# VerticalKeyStrip.net
KiCad netlist of a schematic drawn in Altium Designer
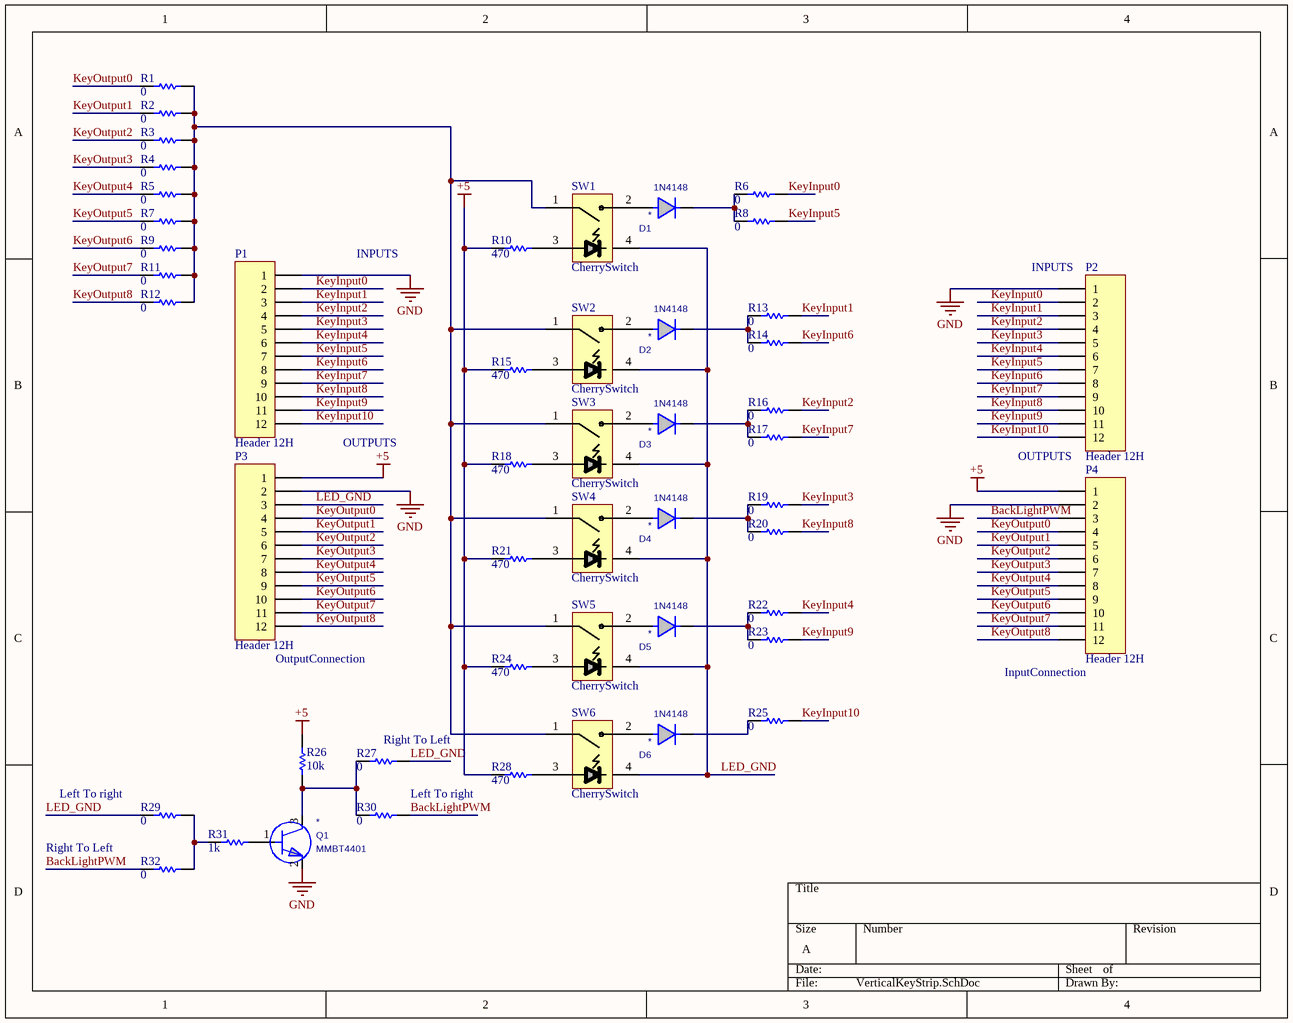
[diagram p0: VerticalKeyStrip.SchDoc]

(export (version "E")
  (design (tool "Eeschema 10.0.6"))
  (components
    (comp (ref "D1")
      (value "1N4148")
      (footprint "DIODE400/60/32")
      (description "Diode, 1N4148, 75V, 0.4 in., DO-35, 150mA, Switching, 500mW, Any")
      (fields (field (name "DNS") "*") (field (name "VOLTAGE") "75V") (field (name "CHECKEDBY") "B. Lyon"))
      (libsource (lib "bome") (part "1N4148"))
    )
    (comp (ref "D2")
      (value "1N4148")
      (footprint "DIODE400/60/32")
      (description "Diode, 1N4148, 75V, 0.4 in., DO-35, 150mA, Switching, 500mW, Any")
      (fields (field (name "DNS") "*") (field (name "VOLTAGE") "75V") (field (name "CHECKEDBY") "B. Lyon"))
      (libsource (lib "bome") (part "1N4148"))
    )
    (comp (ref "D3")
      (value "1N4148")
      (footprint "DIODE400/60/32")
      (description "Diode, 1N4148, 75V, 0.4 in., DO-35, 150mA, Switching, 500mW, Any")
      (fields (field (name "DNS") "*") (field (name "VOLTAGE") "75V") (field (name "CHECKEDBY") "B. Lyon"))
      (libsource (lib "bome") (part "1N4148"))
    )
    (comp (ref "D4")
      (value "1N4148")
      (footprint "DIODE400/60/32")
      (description "Diode, 1N4148, 75V, 0.4 in., DO-35, 150mA, Switching, 500mW, Any")
      (fields (field (name "DNS") "*") (field (name "VOLTAGE") "75V") (field (name "CHECKEDBY") "B. Lyon"))
      (libsource (lib "bome") (part "1N4148"))
    )
    (comp (ref "D5")
      (value "1N4148")
      (footprint "DIODE400/60/32")
      (description "Diode, 1N4148, 75V, 0.4 in., DO-35, 150mA, Switching, 500mW, Any")
      (fields (field (name "DNS") "*") (field (name "VOLTAGE") "75V") (field (name "CHECKEDBY") "B. Lyon"))
      (libsource (lib "bome") (part "1N4148"))
    )
    (comp (ref "D6")
      (value "1N4148")
      (footprint "DIODE400/60/32")
      (description "Diode, 1N4148, 75V, 0.4 in., DO-35, 150mA, Switching, 500mW, Any")
      (fields (field (name "DNS") "*") (field (name "VOLTAGE") "75V") (field (name "CHECKEDBY") "B. Lyon"))
      (libsource (lib "bome") (part "1N4148"))
    )
    (comp (ref "P1")
      (value "Header 12H")
      (footprint "HDR1X12H")
      (description "Header, 12-Pin, Right Angle")
      (fields (field (name "PUBLISHER") "Altium Limited"))
      (libsource (lib "Miscellaneous Connectors") (part "Header 12H"))
    )
    (comp (ref "P2")
      (value "Header 12H")
      (footprint "HDR1X12H")
      (description "Header, 12-Pin, Right Angle")
      (fields (field (name "PUBLISHER") "Altium Limited"))
      (libsource (lib "") (part "Header 12H_1"))
    )
    (comp (ref "P3")
      (value "Header 12H")
      (footprint "HDR1X12H")
      (description "Header, 12-Pin, Right Angle")
      (fields (field (name "PUBLISHER") "Altium Limited"))
      (libsource (lib "Miscellaneous Connectors") (part "Header 12H"))
    )
    (comp (ref "P4")
      (value "Header 12H")
      (footprint "HDR1X12H")
      (description "Header, 12-Pin, Right Angle")
      (fields (field (name "PUBLISHER") "Altium Limited"))
      (libsource (lib "") (part "Header 12H_1"))
    )
    (comp (ref "Q1")
      (value "MMBT4401")
      (footprint "SOT23-3")
      (description "Transistor, MMBT4401, 40V, SOT23-3, 500mA, NPN, Transistor, On Semi: MMBT4401LT1")
      (fields
        (field (name "DNS") "*")
        (field (name "VOLTAGE") "40V")
        (field (name "Comment") "NPN_TRANSISTOR")
        (field (name "CHECKEDBY") "gdeguzman")
        (field (name "CREATEDBY") "Mike Tyger")
        (field (name "LASTUPDATEDBY") "Mike Tyger")
      )
      (libsource (lib "bome") (part "NPN_TRANSISTOR"))
    )
    (comp (ref "R1")
      (value "0")
      (footprint "RESC2012L")
      (description "Semiconductor Resistor")
      (fields (field (name "Comment") "Res Semi") (field (name "PUBLISHER") "Altium Limited"))
      (libsource (lib "Miscellaneous Devices") (part "Res Semi"))
    )
    (comp (ref "R2")
      (value "0")
      (footprint "RESC2012L")
      (description "Semiconductor Resistor")
      (fields (field (name "Comment") "Res Semi") (field (name "PUBLISHER") "Altium Limited"))
      (libsource (lib "Miscellaneous Devices") (part "Res Semi"))
    )
    (comp (ref "R3")
      (value "0")
      (footprint "RESC2012L")
      (description "Semiconductor Resistor")
      (fields (field (name "Comment") "Res Semi") (field (name "PUBLISHER") "Altium Limited"))
      (libsource (lib "Miscellaneous Devices") (part "Res Semi"))
    )
    (comp (ref "R4")
      (value "0")
      (footprint "RESC2012L")
      (description "Semiconductor Resistor")
      (fields (field (name "Comment") "Res Semi") (field (name "PUBLISHER") "Altium Limited"))
      (libsource (lib "Miscellaneous Devices") (part "Res Semi"))
    )
    (comp (ref "R5")
      (value "0")
      (footprint "RESC2012L")
      (description "Semiconductor Resistor")
      (fields (field (name "Comment") "Res Semi") (field (name "PUBLISHER") "Altium Limited"))
      (libsource (lib "Miscellaneous Devices") (part "Res Semi"))
    )
    (comp (ref "R6")
      (value "0")
      (footprint "RESC2012L")
      (description "Semiconductor Resistor")
      (fields (field (name "Comment") "Res Semi") (field (name "PUBLISHER") "Altium Limited"))
      (libsource (lib "Miscellaneous Devices") (part "Res Semi"))
    )
    (comp (ref "R7")
      (value "0")
      (footprint "RESC2012L")
      (description "Semiconductor Resistor")
      (fields (field (name "Comment") "Res Semi") (field (name "PUBLISHER") "Altium Limited"))
      (libsource (lib "Miscellaneous Devices") (part "Res Semi"))
    )
    (comp (ref "R8")
      (value "0")
      (footprint "RESC2012L")
      (description "Semiconductor Resistor")
      (fields (field (name "Comment") "Res Semi") (field (name "PUBLISHER") "Altium Limited"))
      (libsource (lib "Miscellaneous Devices") (part "Res Semi"))
    )
    (comp (ref "R9")
      (value "0")
      (footprint "RESC2012L")
      (description "Semiconductor Resistor")
      (fields (field (name "Comment") "Res Semi") (field (name "PUBLISHER") "Altium Limited"))
      (libsource (lib "Miscellaneous Devices") (part "Res Semi"))
    )
    (comp (ref "R10")
      (value "470")
      (footprint "RESC2012L")
      (description "Semiconductor Resistor")
      (fields (field (name "Comment") "Res Semi") (field (name "PUBLISHER") "Altium Limited"))
      (libsource (lib "Miscellaneous Devices") (part "Res Semi"))
    )
    (comp (ref "R11")
      (value "0")
      (footprint "RESC2012L")
      (description "Semiconductor Resistor")
      (fields (field (name "Comment") "Res Semi") (field (name "PUBLISHER") "Altium Limited"))
      (libsource (lib "Miscellaneous Devices") (part "Res Semi"))
    )
    (comp (ref "R12")
      (value "0")
      (footprint "RESC2012L")
      (description "Semiconductor Resistor")
      (fields (field (name "Comment") "Res Semi") (field (name "PUBLISHER") "Altium Limited"))
      (libsource (lib "Miscellaneous Devices") (part "Res Semi"))
    )
    (comp (ref "R13")
      (value "0")
      (footprint "RESC2012L")
      (description "Semiconductor Resistor")
      (fields (field (name "Comment") "Res Semi") (field (name "PUBLISHER") "Altium Limited"))
      (libsource (lib "Miscellaneous Devices") (part "Res Semi"))
    )
    (comp (ref "R14")
      (value "0")
      (footprint "RESC2012L")
      (description "Semiconductor Resistor")
      (fields (field (name "Comment") "Res Semi") (field (name "PUBLISHER") "Altium Limited"))
      (libsource (lib "Miscellaneous Devices") (part "Res Semi"))
    )
    (comp (ref "R15")
      (value "470")
      (footprint "RESC2012L")
      (description "Semiconductor Resistor")
      (fields (field (name "Comment") "Res Semi") (field (name "PUBLISHER") "Altium Limited"))
      (libsource (lib "Miscellaneous Devices") (part "Res Semi"))
    )
    (comp (ref "R16")
      (value "0")
      (footprint "RESC2012L")
      (description "Semiconductor Resistor")
      (fields (field (name "Comment") "Res Semi") (field (name "PUBLISHER") "Altium Limited"))
      (libsource (lib "Miscellaneous Devices") (part "Res Semi"))
    )
    (comp (ref "R17")
      (value "0")
      (footprint "RESC2012L")
      (description "Semiconductor Resistor")
      (fields (field (name "Comment") "Res Semi") (field (name "PUBLISHER") "Altium Limited"))
      (libsource (lib "Miscellaneous Devices") (part "Res Semi"))
    )
    (comp (ref "R18")
      (value "470")
      (footprint "RESC2012L")
      (description "Semiconductor Resistor")
      (fields (field (name "Comment") "Res Semi") (field (name "PUBLISHER") "Altium Limited"))
      (libsource (lib "Miscellaneous Devices") (part "Res Semi"))
    )
    (comp (ref "R19")
      (value "0")
      (footprint "RESC2012L")
      (description "Semiconductor Resistor")
      (fields (field (name "Comment") "Res Semi") (field (name "PUBLISHER") "Altium Limited"))
      (libsource (lib "Miscellaneous Devices") (part "Res Semi"))
    )
    (comp (ref "R20")
      (value "0")
      (footprint "RESC2012L")
      (description "Semiconductor Resistor")
      (fields (field (name "Comment") "Res Semi") (field (name "PUBLISHER") "Altium Limited"))
      (libsource (lib "Miscellaneous Devices") (part "Res Semi"))
    )
    (comp (ref "R21")
      (value "470")
      (footprint "RESC2012L")
      (description "Semiconductor Resistor")
      (fields (field (name "Comment") "Res Semi") (field (name "PUBLISHER") "Altium Limited"))
      (libsource (lib "Miscellaneous Devices") (part "Res Semi"))
    )
    (comp (ref "R22")
      (value "0")
      (footprint "RESC2012L")
      (description "Semiconductor Resistor")
      (fields (field (name "Comment") "Res Semi") (field (name "PUBLISHER") "Altium Limited"))
      (libsource (lib "Miscellaneous Devices") (part "Res Semi"))
    )
    (comp (ref "R23")
      (value "0")
      (footprint "RESC2012L")
      (description "Semiconductor Resistor")
      (fields (field (name "Comment") "Res Semi") (field (name "PUBLISHER") "Altium Limited"))
      (libsource (lib "Miscellaneous Devices") (part "Res Semi"))
    )
    (comp (ref "R24")
      (value "470")
      (footprint "RESC2012L")
      (description "Semiconductor Resistor")
      (fields (field (name "Comment") "Res Semi") (field (name "PUBLISHER") "Altium Limited"))
      (libsource (lib "Miscellaneous Devices") (part "Res Semi"))
    )
    (comp (ref "R25")
      (value "0")
      (footprint "RESC2012L")
      (description "Semiconductor Resistor")
      (fields (field (name "Comment") "Res Semi") (field (name "PUBLISHER") "Altium Limited"))
      (libsource (lib "Miscellaneous Devices") (part "Res Semi"))
    )
    (comp (ref "R26")
      (value "10k")
      (footprint "RESC2012L")
      (description "Semiconductor Resistor")
      (fields (field (name "Comment") "Res Semi") (field (name "PUBLISHER") "Altium Limited"))
      (libsource (lib "Miscellaneous Devices") (part "Res Semi"))
    )
    (comp (ref "R27")
      (value "0")
      (footprint "RESC2012L")
      (description "Semiconductor Resistor")
      (fields (field (name "Comment") "Res Semi") (field (name "PUBLISHER") "Altium Limited"))
      (libsource (lib "Miscellaneous Devices") (part "Res Semi"))
    )
    (comp (ref "R28")
      (value "470")
      (footprint "RESC2012L")
      (description "Semiconductor Resistor")
      (fields (field (name "Comment") "Res Semi") (field (name "PUBLISHER") "Altium Limited"))
      (libsource (lib "Miscellaneous Devices") (part "Res Semi"))
    )
    (comp (ref "R29")
      (value "0")
      (footprint "RESC2012L")
      (description "Semiconductor Resistor")
      (fields (field (name "Comment") "Res Semi") (field (name "PUBLISHER") "Altium Limited"))
      (libsource (lib "Miscellaneous Devices") (part "Res Semi"))
    )
    (comp (ref "R30")
      (value "0")
      (footprint "RESC2012L")
      (description "Semiconductor Resistor")
      (fields (field (name "Comment") "Res Semi") (field (name "PUBLISHER") "Altium Limited"))
      (libsource (lib "Miscellaneous Devices") (part "Res Semi"))
    )
    (comp (ref "R31")
      (value "1k")
      (footprint "RESC2012L")
      (description "Semiconductor Resistor")
      (fields (field (name "Comment") "Res Semi") (field (name "PUBLISHER") "Altium Limited"))
      (libsource (lib "Miscellaneous Devices") (part "Res Semi"))
    )
    (comp (ref "R32")
      (value "0")
      (footprint "RESC2012L")
      (description "Semiconductor Resistor")
      (fields (field (name "Comment") "Res Semi") (field (name "PUBLISHER") "Altium Limited"))
      (libsource (lib "Miscellaneous Devices") (part "Res Semi"))
    )
    (comp (ref "SW1")
      (value "CherrySwitch")
      (footprint "CherryMxSwitch")
      (description "Cherry MX Switch layout")
      (libsource (lib "mainBoardLib") (part "CherrySwitch"))
    )
    (comp (ref "SW2")
      (value "CherrySwitch")
      (footprint "CherryMxSwitch")
      (description "Cherry MX Switch layout")
      (libsource (lib "mainBoardLib") (part "CherrySwitch"))
    )
    (comp (ref "SW3")
      (value "CherrySwitch")
      (footprint "CherryMxSwitch")
      (description "Cherry MX Switch layout")
      (libsource (lib "mainBoardLib") (part "CherrySwitch"))
    )
    (comp (ref "SW4")
      (value "CherrySwitch")
      (footprint "CherryMxSwitch")
      (description "Cherry MX Switch layout")
      (libsource (lib "mainBoardLib") (part "CherrySwitch"))
    )
    (comp (ref "SW5")
      (value "CherrySwitch")
      (footprint "CherryMxSwitch")
      (description "Cherry MX Switch layout")
      (libsource (lib "mainBoardLib") (part "CherrySwitch"))
    )
    (comp (ref "SW6")
      (value "CherrySwitch")
      (footprint "CherryMxSwitch")
      (description "Cherry MX Switch layout")
      (libsource (lib "mainBoardLib") (part "CherrySwitch"))
    )
  )
  (nets
    (net (code "1") (name "+5") (class "Default")
      (node (ref "P3") (pin "1") (pinfunction "1_1") (pintype "passive"))
      (node (ref "P4") (pin "1") (pinfunction "1_1") (pintype "passive"))
      (node (ref "R10") (pin "1") (pinfunction "1_1") (pintype "passive"))
      (node (ref "R15") (pin "1") (pinfunction "1_1") (pintype "passive"))
      (node (ref "R18") (pin "1") (pinfunction "1_1") (pintype "passive"))
      (node (ref "R21") (pin "1") (pinfunction "1_1") (pintype "passive"))
      (node (ref "R24") (pin "1") (pinfunction "1_1") (pintype "passive"))
      (node (ref "R26") (pin "2") (pinfunction "2_2") (pintype "passive"))
      (node (ref "R28") (pin "1") (pinfunction "1_1") (pintype "passive"))
    )
    (net (code "2") (name "/BackLightPWM") (class "Default")
      (node (ref "P4") (pin "3") (pinfunction "3_3") (pintype "passive"))
      (node (ref "R30") (pin "2") (pinfunction "2_2") (pintype "passive"))
      (node (ref "R32") (pin "1") (pinfunction "1_1") (pintype "passive"))
    )
    (net (code "3") (name "/KeyInput0") (class "Default")
      (node (ref "P1") (pin "2") (pinfunction "2_2") (pintype "passive"))
      (node (ref "P2") (pin "2") (pinfunction "2_2") (pintype "passive"))
      (node (ref "R6") (pin "2") (pinfunction "2_2") (pintype "passive"))
    )
    (net (code "4") (name "/KeyInput1") (class "Default")
      (node (ref "P1") (pin "3") (pinfunction "3_3") (pintype "passive"))
      (node (ref "P2") (pin "3") (pinfunction "3_3") (pintype "passive"))
      (node (ref "R13") (pin "2") (pinfunction "2_2") (pintype "passive"))
    )
    (net (code "5") (name "/KeyInput2") (class "Default")
      (node (ref "P1") (pin "4") (pinfunction "4_4") (pintype "passive"))
      (node (ref "P2") (pin "4") (pinfunction "4_4") (pintype "passive"))
      (node (ref "R16") (pin "2") (pinfunction "2_2") (pintype "passive"))
    )
    (net (code "6") (name "/KeyInput3") (class "Default")
      (node (ref "P1") (pin "5") (pinfunction "5_5") (pintype "passive"))
      (node (ref "P2") (pin "5") (pinfunction "5_5") (pintype "passive"))
      (node (ref "R19") (pin "2") (pinfunction "2_2") (pintype "passive"))
    )
    (net (code "7") (name "/KeyInput4") (class "Default")
      (node (ref "P1") (pin "6") (pinfunction "6_6") (pintype "passive"))
      (node (ref "P2") (pin "6") (pinfunction "6_6") (pintype "passive"))
      (node (ref "R22") (pin "2") (pinfunction "2_2") (pintype "passive"))
    )
    (net (code "8") (name "/KeyInput5") (class "Default")
      (node (ref "P1") (pin "7") (pinfunction "7_7") (pintype "passive"))
      (node (ref "P2") (pin "7") (pinfunction "7_7") (pintype "passive"))
      (node (ref "R8") (pin "2") (pinfunction "2_2") (pintype "passive"))
    )
    (net (code "9") (name "/KeyInput6") (class "Default")
      (node (ref "P1") (pin "8") (pinfunction "8_8") (pintype "passive"))
      (node (ref "P2") (pin "8") (pinfunction "8_8") (pintype "passive"))
      (node (ref "R14") (pin "2") (pinfunction "2_2") (pintype "passive"))
    )
    (net (code "10") (name "/KeyInput7") (class "Default")
      (node (ref "P1") (pin "9") (pinfunction "9_9") (pintype "passive"))
      (node (ref "P2") (pin "9") (pinfunction "9_9") (pintype "passive"))
      (node (ref "R17") (pin "2") (pinfunction "2_2") (pintype "passive"))
    )
    (net (code "11") (name "/KeyInput8") (class "Default")
      (node (ref "P1") (pin "10") (pinfunction "10_10") (pintype "passive"))
      (node (ref "P2") (pin "10") (pinfunction "10_10") (pintype "passive"))
      (node (ref "R20") (pin "2") (pinfunction "2_2") (pintype "passive"))
    )
    (net (code "12") (name "/KeyInput9") (class "Default")
      (node (ref "P1") (pin "11") (pinfunction "11_11") (pintype "passive"))
      (node (ref "P2") (pin "11") (pinfunction "11_11") (pintype "passive"))
      (node (ref "R23") (pin "2") (pinfunction "2_2") (pintype "passive"))
    )
    (net (code "13") (name "/KeyInput10") (class "Default")
      (node (ref "P1") (pin "12") (pinfunction "12_12") (pintype "passive"))
      (node (ref "P2") (pin "12") (pinfunction "12_12") (pintype "passive"))
      (node (ref "R25") (pin "2") (pinfunction "2_2") (pintype "passive"))
    )
    (net (code "14") (name "/KeyOutput0") (class "Default")
      (node (ref "P3") (pin "4") (pinfunction "4_4") (pintype "passive"))
      (node (ref "P4") (pin "4") (pinfunction "4_4") (pintype "passive"))
      (node (ref "R1") (pin "1") (pinfunction "1_1") (pintype "passive"))
    )
    (net (code "15") (name "/KeyOutput1") (class "Default")
      (node (ref "P3") (pin "5") (pinfunction "5_5") (pintype "passive"))
      (node (ref "P4") (pin "5") (pinfunction "5_5") (pintype "passive"))
      (node (ref "R2") (pin "1") (pinfunction "1_1") (pintype "passive"))
    )
    (net (code "16") (name "/KeyOutput2") (class "Default")
      (node (ref "P3") (pin "6") (pinfunction "6_6") (pintype "passive"))
      (node (ref "P4") (pin "6") (pinfunction "6_6") (pintype "passive"))
      (node (ref "R3") (pin "1") (pinfunction "1_1") (pintype "passive"))
    )
    (net (code "17") (name "/KeyOutput3") (class "Default")
      (node (ref "P3") (pin "7") (pinfunction "7_7") (pintype "passive"))
      (node (ref "P4") (pin "7") (pinfunction "7_7") (pintype "passive"))
      (node (ref "R4") (pin "1") (pinfunction "1_1") (pintype "passive"))
    )
    (net (code "18") (name "/KeyOutput4") (class "Default")
      (node (ref "P3") (pin "8") (pinfunction "8_8") (pintype "passive"))
      (node (ref "P4") (pin "8") (pinfunction "8_8") (pintype "passive"))
      (node (ref "R5") (pin "1") (pinfunction "1_1") (pintype "passive"))
    )
    (net (code "19") (name "/KeyOutput5") (class "Default")
      (node (ref "P3") (pin "9") (pinfunction "9_9") (pintype "passive"))
      (node (ref "P4") (pin "9") (pinfunction "9_9") (pintype "passive"))
      (node (ref "R7") (pin "1") (pinfunction "1_1") (pintype "passive"))
    )
    (net (code "20") (name "/KeyOutput6") (class "Default")
      (node (ref "P3") (pin "10") (pinfunction "10_10") (pintype "passive"))
      (node (ref "P4") (pin "10") (pinfunction "10_10") (pintype "passive"))
      (node (ref "R9") (pin "1") (pinfunction "1_1") (pintype "passive"))
    )
    (net (code "21") (name "/KeyOutput7") (class "Default")
      (node (ref "P3") (pin "11") (pinfunction "11_11") (pintype "passive"))
      (node (ref "P4") (pin "11") (pinfunction "11_11") (pintype "passive"))
      (node (ref "R11") (pin "1") (pinfunction "1_1") (pintype "passive"))
    )
    (net (code "22") (name "/KeyOutput8") (class "Default")
      (node (ref "P3") (pin "12") (pinfunction "12_12") (pintype "passive"))
      (node (ref "P4") (pin "12") (pinfunction "12_12") (pintype "passive"))
      (node (ref "R12") (pin "1") (pinfunction "1_1") (pintype "passive"))
    )
    (net (code "23") (name "/LED_GND") (class "Default")
      (node (ref "P3") (pin "3") (pinfunction "3_3") (pintype "passive"))
      (node (ref "R27") (pin "2") (pinfunction "2_2") (pintype "passive"))
      (node (ref "R29") (pin "1") (pinfunction "1_1") (pintype "passive"))
      (node (ref "SW1") (pin "4") (pinfunction "4_4") (pintype "passive"))
      (node (ref "SW2") (pin "4") (pinfunction "4_4") (pintype "passive"))
      (node (ref "SW3") (pin "4") (pinfunction "4_4") (pintype "passive"))
      (node (ref "SW4") (pin "4") (pinfunction "4_4") (pintype "passive"))
      (node (ref "SW5") (pin "4") (pinfunction "4_4") (pintype "passive"))
      (node (ref "SW6") (pin "4") (pinfunction "4_4") (pintype "passive"))
    )
    (net (code "24") (name "GND") (class "Default")
      (node (ref "P1") (pin "1") (pinfunction "1_1") (pintype "passive"))
      (node (ref "P2") (pin "1") (pinfunction "1_1") (pintype "passive"))
      (node (ref "P3") (pin "2") (pinfunction "2_2") (pintype "passive"))
      (node (ref "P4") (pin "2") (pinfunction "2_2") (pintype "passive"))
      (node (ref "Q1") (pin "2") (pinfunction "emitter_2") (pintype "passive"))
    )
    (net (code "25") (name "Net-(D1-ANODE)") (class "Default")
      (node (ref "D1") (pin "2") (pinfunction "ANODE_2") (pintype "passive"))
      (node (ref "SW1") (pin "2") (pinfunction "2_2") (pintype "passive"))
    )
    (net (code "26") (name "Net-(D1-CATHODE)") (class "Default")
      (node (ref "D1") (pin "1") (pinfunction "CATHODE_1") (pintype "passive"))
      (node (ref "R6") (pin "1") (pinfunction "1_1") (pintype "passive"))
      (node (ref "R8") (pin "1") (pinfunction "1_1") (pintype "passive"))
    )
    (net (code "27") (name "Net-(D2-ANODE)") (class "Default")
      (node (ref "D2") (pin "2") (pinfunction "ANODE_2") (pintype "passive"))
      (node (ref "SW2") (pin "2") (pinfunction "2_2") (pintype "passive"))
    )
    (net (code "28") (name "Net-(D2-CATHODE)") (class "Default")
      (node (ref "D2") (pin "1") (pinfunction "CATHODE_1") (pintype "passive"))
      (node (ref "R13") (pin "1") (pinfunction "1_1") (pintype "passive"))
      (node (ref "R14") (pin "1") (pinfunction "1_1") (pintype "passive"))
    )
    (net (code "29") (name "Net-(D3-ANODE)") (class "Default")
      (node (ref "D3") (pin "2") (pinfunction "ANODE_2") (pintype "passive"))
      (node (ref "SW3") (pin "2") (pinfunction "2_2") (pintype "passive"))
    )
    (net (code "30") (name "Net-(D3-CATHODE)") (class "Default")
      (node (ref "D3") (pin "1") (pinfunction "CATHODE_1") (pintype "passive"))
      (node (ref "R16") (pin "1") (pinfunction "1_1") (pintype "passive"))
      (node (ref "R17") (pin "1") (pinfunction "1_1") (pintype "passive"))
    )
    (net (code "31") (name "Net-(D4-ANODE)") (class "Default")
      (node (ref "D4") (pin "2") (pinfunction "ANODE_2") (pintype "passive"))
      (node (ref "SW4") (pin "2") (pinfunction "2_2") (pintype "passive"))
    )
    (net (code "32") (name "Net-(D4-CATHODE)") (class "Default")
      (node (ref "D4") (pin "1") (pinfunction "CATHODE_1") (pintype "passive"))
      (node (ref "R19") (pin "1") (pinfunction "1_1") (pintype "passive"))
      (node (ref "R20") (pin "1") (pinfunction "1_1") (pintype "passive"))
    )
    (net (code "33") (name "Net-(D5-ANODE)") (class "Default")
      (node (ref "D5") (pin "2") (pinfunction "ANODE_2") (pintype "passive"))
      (node (ref "SW5") (pin "2") (pinfunction "2_2") (pintype "passive"))
    )
    (net (code "34") (name "Net-(D5-CATHODE)") (class "Default")
      (node (ref "D5") (pin "1") (pinfunction "CATHODE_1") (pintype "passive"))
      (node (ref "R22") (pin "1") (pinfunction "1_1") (pintype "passive"))
      (node (ref "R23") (pin "1") (pinfunction "1_1") (pintype "passive"))
    )
    (net (code "35") (name "Net-(D6-ANODE)") (class "Default")
      (node (ref "D6") (pin "2") (pinfunction "ANODE_2") (pintype "passive"))
      (node (ref "SW6") (pin "2") (pinfunction "2_2") (pintype "passive"))
    )
    (net (code "36") (name "Net-(D6-CATHODE)") (class "Default")
      (node (ref "D6") (pin "1") (pinfunction "CATHODE_1") (pintype "passive"))
      (node (ref "R25") (pin "1") (pinfunction "1_1") (pintype "passive"))
    )
    (net (code "37") (name "Net-(Q1-base)") (class "Default")
      (node (ref "Q1") (pin "1") (pinfunction "base_1") (pintype "passive"))
      (node (ref "R31") (pin "2") (pinfunction "2_2") (pintype "passive"))
    )
    (net (code "38") (name "Net-(Q1-collector)") (class "Default")
      (node (ref "Q1") (pin "3") (pinfunction "collector_3") (pintype "passive"))
      (node (ref "R26") (pin "1") (pinfunction "1_1") (pintype "passive"))
      (node (ref "R27") (pin "1") (pinfunction "1_1") (pintype "passive"))
      (node (ref "R30") (pin "1") (pinfunction "1_1") (pintype "passive"))
    )
    (net (code "39") (name "Net-(R1-Pad2)") (class "Default")
      (node (ref "R1") (pin "2") (pinfunction "2_2") (pintype "passive"))
      (node (ref "R11") (pin "2") (pinfunction "2_2") (pintype "passive"))
      (node (ref "R12") (pin "2") (pinfunction "2_2") (pintype "passive"))
      (node (ref "R2") (pin "2") (pinfunction "2_2") (pintype "passive"))
      (node (ref "R3") (pin "2") (pinfunction "2_2") (pintype "passive"))
      (node (ref "R4") (pin "2") (pinfunction "2_2") (pintype "passive"))
      (node (ref "R5") (pin "2") (pinfunction "2_2") (pintype "passive"))
      (node (ref "R7") (pin "2") (pinfunction "2_2") (pintype "passive"))
      (node (ref "R9") (pin "2") (pinfunction "2_2") (pintype "passive"))
      (node (ref "SW1") (pin "1") (pinfunction "1_1") (pintype "passive"))
      (node (ref "SW2") (pin "1") (pinfunction "1_1") (pintype "passive"))
      (node (ref "SW3") (pin "1") (pinfunction "1_1") (pintype "passive"))
      (node (ref "SW4") (pin "1") (pinfunction "1_1") (pintype "passive"))
      (node (ref "SW5") (pin "1") (pinfunction "1_1") (pintype "passive"))
      (node (ref "SW6") (pin "1") (pinfunction "1_1") (pintype "passive"))
    )
    (net (code "40") (name "Net-(R10-Pad2)") (class "Default")
      (node (ref "R10") (pin "2") (pinfunction "2_2") (pintype "passive"))
      (node (ref "SW1") (pin "3") (pinfunction "3_3") (pintype "passive"))
    )
    (net (code "41") (name "Net-(R15-Pad2)") (class "Default")
      (node (ref "R15") (pin "2") (pinfunction "2_2") (pintype "passive"))
      (node (ref "SW2") (pin "3") (pinfunction "3_3") (pintype "passive"))
    )
    (net (code "42") (name "Net-(R18-Pad2)") (class "Default")
      (node (ref "R18") (pin "2") (pinfunction "2_2") (pintype "passive"))
      (node (ref "SW3") (pin "3") (pinfunction "3_3") (pintype "passive"))
    )
    (net (code "43") (name "Net-(R21-Pad2)") (class "Default")
      (node (ref "R21") (pin "2") (pinfunction "2_2") (pintype "passive"))
      (node (ref "SW4") (pin "3") (pinfunction "3_3") (pintype "passive"))
    )
    (net (code "44") (name "Net-(R24-Pad2)") (class "Default")
      (node (ref "R24") (pin "2") (pinfunction "2_2") (pintype "passive"))
      (node (ref "SW5") (pin "3") (pinfunction "3_3") (pintype "passive"))
    )
    (net (code "45") (name "Net-(R28-Pad2)") (class "Default")
      (node (ref "R28") (pin "2") (pinfunction "2_2") (pintype "passive"))
      (node (ref "SW6") (pin "3") (pinfunction "3_3") (pintype "passive"))
    )
    (net (code "46") (name "Net-(R29-Pad2)") (class "Default")
      (node (ref "R29") (pin "2") (pinfunction "2_2") (pintype "passive"))
      (node (ref "R31") (pin "1") (pinfunction "1_1") (pintype "passive"))
      (node (ref "R32") (pin "2") (pinfunction "2_2") (pintype "passive"))
    )
  )
)
